# Supply.net
KiCad netlist of a schematic drawn in Altium Designer
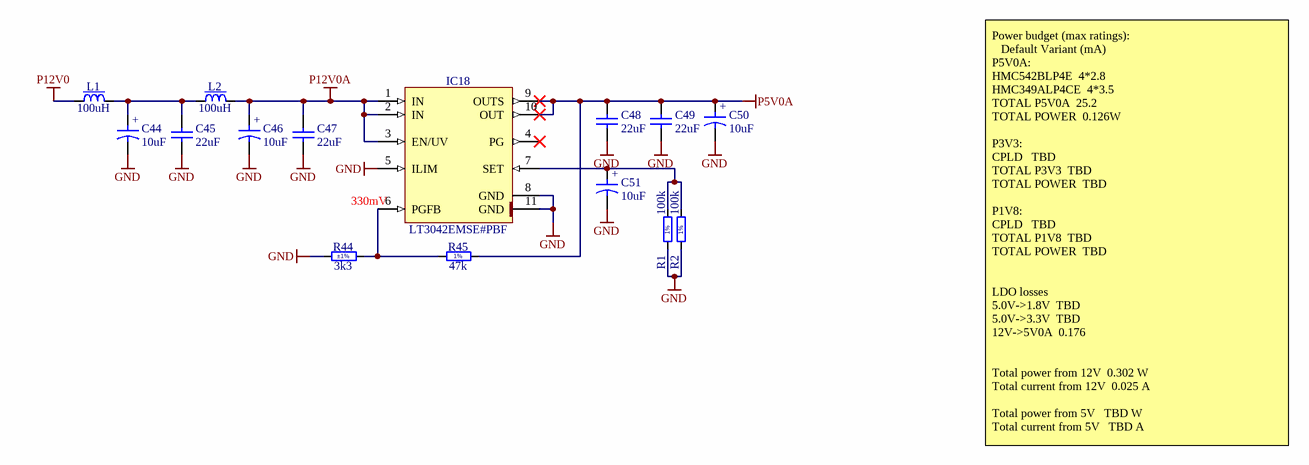
[diagram p0: Supply.SchDoc]

(export (version "E")
  (design (tool "Eeschema 10.0.6"))
  (components
    (comp (ref "C44")
      (value "10uF")
      (footprint "CAPMP3216X180N")
      (description "Polarised capacitor")
      (fields
        (field (name "PART NUMBER") "CTE3216-18_10UF_16V_20%_AVX_TCJ")
        (field (name "VOLTAGE") "16V")
        (field (name "AUTHOR") "CERN DEM JLC")
      )
      (libsource (lib "Capacitors") (part "Capacitor - polarized"))
    )
    (comp (ref "C45")
      (value "22uF")
      (footprint "CAPC2012X135N")
      (description "Non-polarised capacitor")
      (fields
        (field (name "PART NUMBER") "CC0805_22UF_16V_10%_X5R")
        (field (name "VOLTAGE") "16V")
        (field (name "AUTHOR") "CERN DEM JLC")
      )
      (libsource (lib "Capacitors") (part "Capacitor - non polarized"))
    )
    (comp (ref "C46")
      (value "10uF")
      (footprint "CAPMP3216X180N")
      (description "Polarised capacitor")
      (fields
        (field (name "PART NUMBER") "CTE3216-18_10UF_16V_20%_AVX_TCJ")
        (field (name "VOLTAGE") "16V")
        (field (name "AUTHOR") "CERN DEM JLC")
      )
      (libsource (lib "Capacitors") (part "Capacitor - polarized"))
    )
    (comp (ref "C47")
      (value "22uF")
      (footprint "CAPC2012X135N")
      (description "Non-polarised capacitor")
      (fields
        (field (name "PART NUMBER") "CC0805_22UF_16V_10%_X5R")
        (field (name "VOLTAGE") "16V")
        (field (name "AUTHOR") "CERN DEM JLC")
      )
      (libsource (lib "Capacitors") (part "Capacitor - non polarized"))
    )
    (comp (ref "C48")
      (value "22uF")
      (footprint "CAPC2012X135N")
      (description "Non-polarised capacitor")
      (fields
        (field (name "PART NUMBER") "CC0805_22UF_16V_10%_X5R")
        (field (name "VOLTAGE") "16V")
        (field (name "AUTHOR") "CERN DEM JLC")
      )
      (libsource (lib "Capacitors") (part "Capacitor - non polarized"))
    )
    (comp (ref "C49")
      (value "22uF")
      (footprint "CAPC2012X135N")
      (description "Non-polarised capacitor")
      (fields
        (field (name "PART NUMBER") "CC0805_22UF_16V_10%_X5R")
        (field (name "VOLTAGE") "16V")
        (field (name "AUTHOR") "CERN DEM JLC")
      )
      (libsource (lib "Capacitors") (part "Capacitor - non polarized"))
    )
    (comp (ref "C50")
      (value "10uF")
      (footprint "CAPMP3216X180N")
      (description "Polarised capacitor")
      (fields
        (field (name "PART NUMBER") "CTE3216-18_10UF_16V_20%_AVX_TCJ")
        (field (name "VOLTAGE") "16V")
        (field (name "AUTHOR") "CERN DEM JLC")
      )
      (libsource (lib "Capacitors") (part "Capacitor - polarized"))
    )
    (comp (ref "C51")
      (value "10uF")
      (footprint "CAPMP3216X180N")
      (description "Polarised capacitor")
      (fields
        (field (name "PART NUMBER") "CTE3216-18_10UF_16V_20%_AVX_TCJ")
        (field (name "VOLTAGE") "16V")
        (field (name "AUTHOR") "CERN DEM JLC")
      )
      (libsource (lib "Capacitors") (part "Capacitor - polarized"))
    )
    (comp (ref "IC18")
      (value "LT3042EMSE#PBF")
      (footprint "SOP50P490X110-11N-R168X198")
      (description "20V, 200mA, Ultralow Noise, Ultrahigh PSRR RF Linear Regulator")
      (fields (field (name "MANUFACTURER") "LINEAR TECHNOLOGY") (field (name "AUTHOR") "CERN DEM MR"))
      (libsource (lib "ICs And Semiconductors") (part "LT3042"))
    )
    (comp (ref "L1")
      (value "100uH")
      (footprint "INDM5650X530N")
      (description "Inductor With Core")
      (fields
        (field (name "PART NUMBER") "IND2220_100UH_10%_EPCOS_B82442H")
        (field (name "POWER") "350mA")
        (field (name "AUTHOR") "CERN DEM JLC")
      )
      (libsource (lib "Inductors & Transformers") (part "Inductor With Magnetic core"))
    )
    (comp (ref "L2")
      (value "100uH")
      (footprint "INDM5650X530N")
      (description "Inductor With Core")
      (fields
        (field (name "PART NUMBER") "IND2220_100UH_10%_EPCOS_B82442H")
        (field (name "POWER") "350mA")
        (field (name "AUTHOR") "CERN DEM JLC")
      )
      (libsource (lib "Inductors & Transformers") (part "Inductor With Magnetic core"))
    )
    (comp (ref "R1")
      (value "100k")
      (footprint "RESC1005X40N")
      (description "Resistor - 1%")
      (fields
        (field (name "PART NUMBER") "R0402_100K_1%_0.0625W_100PPM")
        (field (name "MANUFACTURER") "GENERIC")
        (field (name "AUTHOR") "CERN DEM JLC")
      )
      (libsource (lib "Resistors") (part "Resistor - 1%"))
    )
    (comp (ref "R2")
      (value "100k")
      (footprint "RESC1005X40N")
      (description "Resistor - 1%")
      (fields
        (field (name "PART NUMBER") "R0402_100K_1%_0.0625W_100PPM")
        (field (name "MANUFACTURER") "GENERIC")
        (field (name "AUTHOR") "CERN DEM JLC")
      )
      (libsource (lib "Resistors") (part "Resistor - 1%"))
    )
    (comp (ref "R44")
      (value "3k3")
      (footprint "RESC1005X40N")
      (description "Resistor - 1%")
      (fields
        (field (name "TOLERANCE") "±1%")
        (field (name "PART NUMBER") "R0402_3K3_1%_0.0625W_100PPM")
        (field (name "POWER") "0.0625W")
        (field (name "AUTHOR") "CERN DEM JLC")
      )
      (libsource (lib "Resistors") (part "Resistor - 1%"))
    )
    (comp (ref "R45")
      (value "47k")
      (footprint "RESC1005X40N")
      (description "Resistor - 1%")
      (fields
        (field (name "PART NUMBER") "R0402_47K_1%_0.0625W_100PPM")
        (field (name "POWER") "0.0625W")
        (field (name "AUTHOR") "CERN DEM JLC")
      )
      (libsource (lib "Resistors") (part "Resistor - 1%"))
    )
  )
  (nets
    (net (code "1") (name "GND") (class "Default")
      (node (ref "C44") (pin "2") (pinfunction "2_2") (pintype "passive"))
      (node (ref "C45") (pin "1") (pinfunction "1_1") (pintype "passive"))
      (node (ref "C46") (pin "2") (pinfunction "2_2") (pintype "passive"))
      (node (ref "C47") (pin "1") (pinfunction "1_1") (pintype "passive"))
      (node (ref "C48") (pin "1") (pinfunction "1_1") (pintype "passive"))
      (node (ref "C49") (pin "1") (pinfunction "1_1") (pintype "passive"))
      (node (ref "C50") (pin "2") (pinfunction "2_2") (pintype "passive"))
      (node (ref "C51") (pin "2") (pinfunction "2_2") (pintype "passive"))
      (node (ref "IC18") (pin "11") (pinfunction "GND_11") (pintype "power_in"))
      (node (ref "IC18") (pin "5") (pinfunction "ILIM_5") (pintype "input"))
      (node (ref "IC18") (pin "8") (pinfunction "GND_8") (pintype "power_in"))
      (node (ref "R1") (pin "2") (pinfunction "2_2") (pintype "passive"))
      (node (ref "R2") (pin "2") (pinfunction "2_2") (pintype "passive"))
      (node (ref "R44") (pin "2") (pinfunction "2_2") (pintype "passive"))
    )
    (net (code "2") (name "Net-(C44-Pad1)") (class "Default")
      (node (ref "C44") (pin "1") (pinfunction "1_1") (pintype "passive"))
      (node (ref "C45") (pin "2") (pinfunction "2_2") (pintype "passive"))
      (node (ref "L1") (pin "2") (pinfunction "2_2") (pintype "passive"))
      (node (ref "L2") (pin "1") (pinfunction "1_1") (pintype "passive"))
    )
    (net (code "3") (name "Net-(IC18-PGFB)") (class "Default")
      (node (ref "IC18") (pin "6") (pinfunction "PGFB_6") (pintype "input"))
      (node (ref "R44") (pin "1") (pinfunction "1_1") (pintype "passive"))
      (node (ref "R45") (pin "1") (pinfunction "1_1") (pintype "passive"))
    )
    (net (code "4") (name "Net-(IC18-SET)") (class "Default")
      (node (ref "C51") (pin "1") (pinfunction "1_1") (pintype "passive"))
      (node (ref "IC18") (pin "7") (pinfunction "SET_7") (pintype "input"))
      (node (ref "R1") (pin "1") (pinfunction "1_1") (pintype "passive"))
      (node (ref "R2") (pin "1") (pinfunction "1_1") (pintype "passive"))
    )
    (net (code "5") (name "P5V0A") (class "Default")
      (node (ref "C48") (pin "2") (pinfunction "2_2") (pintype "passive"))
      (node (ref "C49") (pin "2") (pinfunction "2_2") (pintype "passive"))
      (node (ref "C50") (pin "1") (pinfunction "1_1") (pintype "passive"))
      (node (ref "IC18") (pin "10") (pinfunction "OUT_10") (pintype "output"))
      (node (ref "IC18") (pin "9") (pinfunction "OUTS_9") (pintype "output"))
      (node (ref "R45") (pin "2") (pinfunction "2_2") (pintype "passive"))
    )
    (net (code "6") (name "P12V0") (class "Default")
      (node (ref "L1") (pin "1") (pinfunction "1_1") (pintype "passive"))
    )
    (net (code "7") (name "P12V0A") (class "Default")
      (node (ref "C46") (pin "1") (pinfunction "1_1") (pintype "passive"))
      (node (ref "C47") (pin "2") (pinfunction "2_2") (pintype "passive"))
      (node (ref "IC18") (pin "1") (pinfunction "IN_1") (pintype "input"))
      (node (ref "IC18") (pin "2") (pinfunction "IN_2") (pintype "input"))
      (node (ref "IC18") (pin "3") (pinfunction "EN/UV_3") (pintype "input"))
      (node (ref "L2") (pin "2") (pinfunction "2_2") (pintype "passive"))
    )
    (net (code "8") (name "unconnected-(IC18-PG-Pad4)") (class "Default")
      (node (ref "IC18") (pin "4") (pinfunction "PG_4") (pintype "output+no_connect"))
    )
  )
)
